# neuron.net
KiCad netlist of a schematic drawn in EAGLE
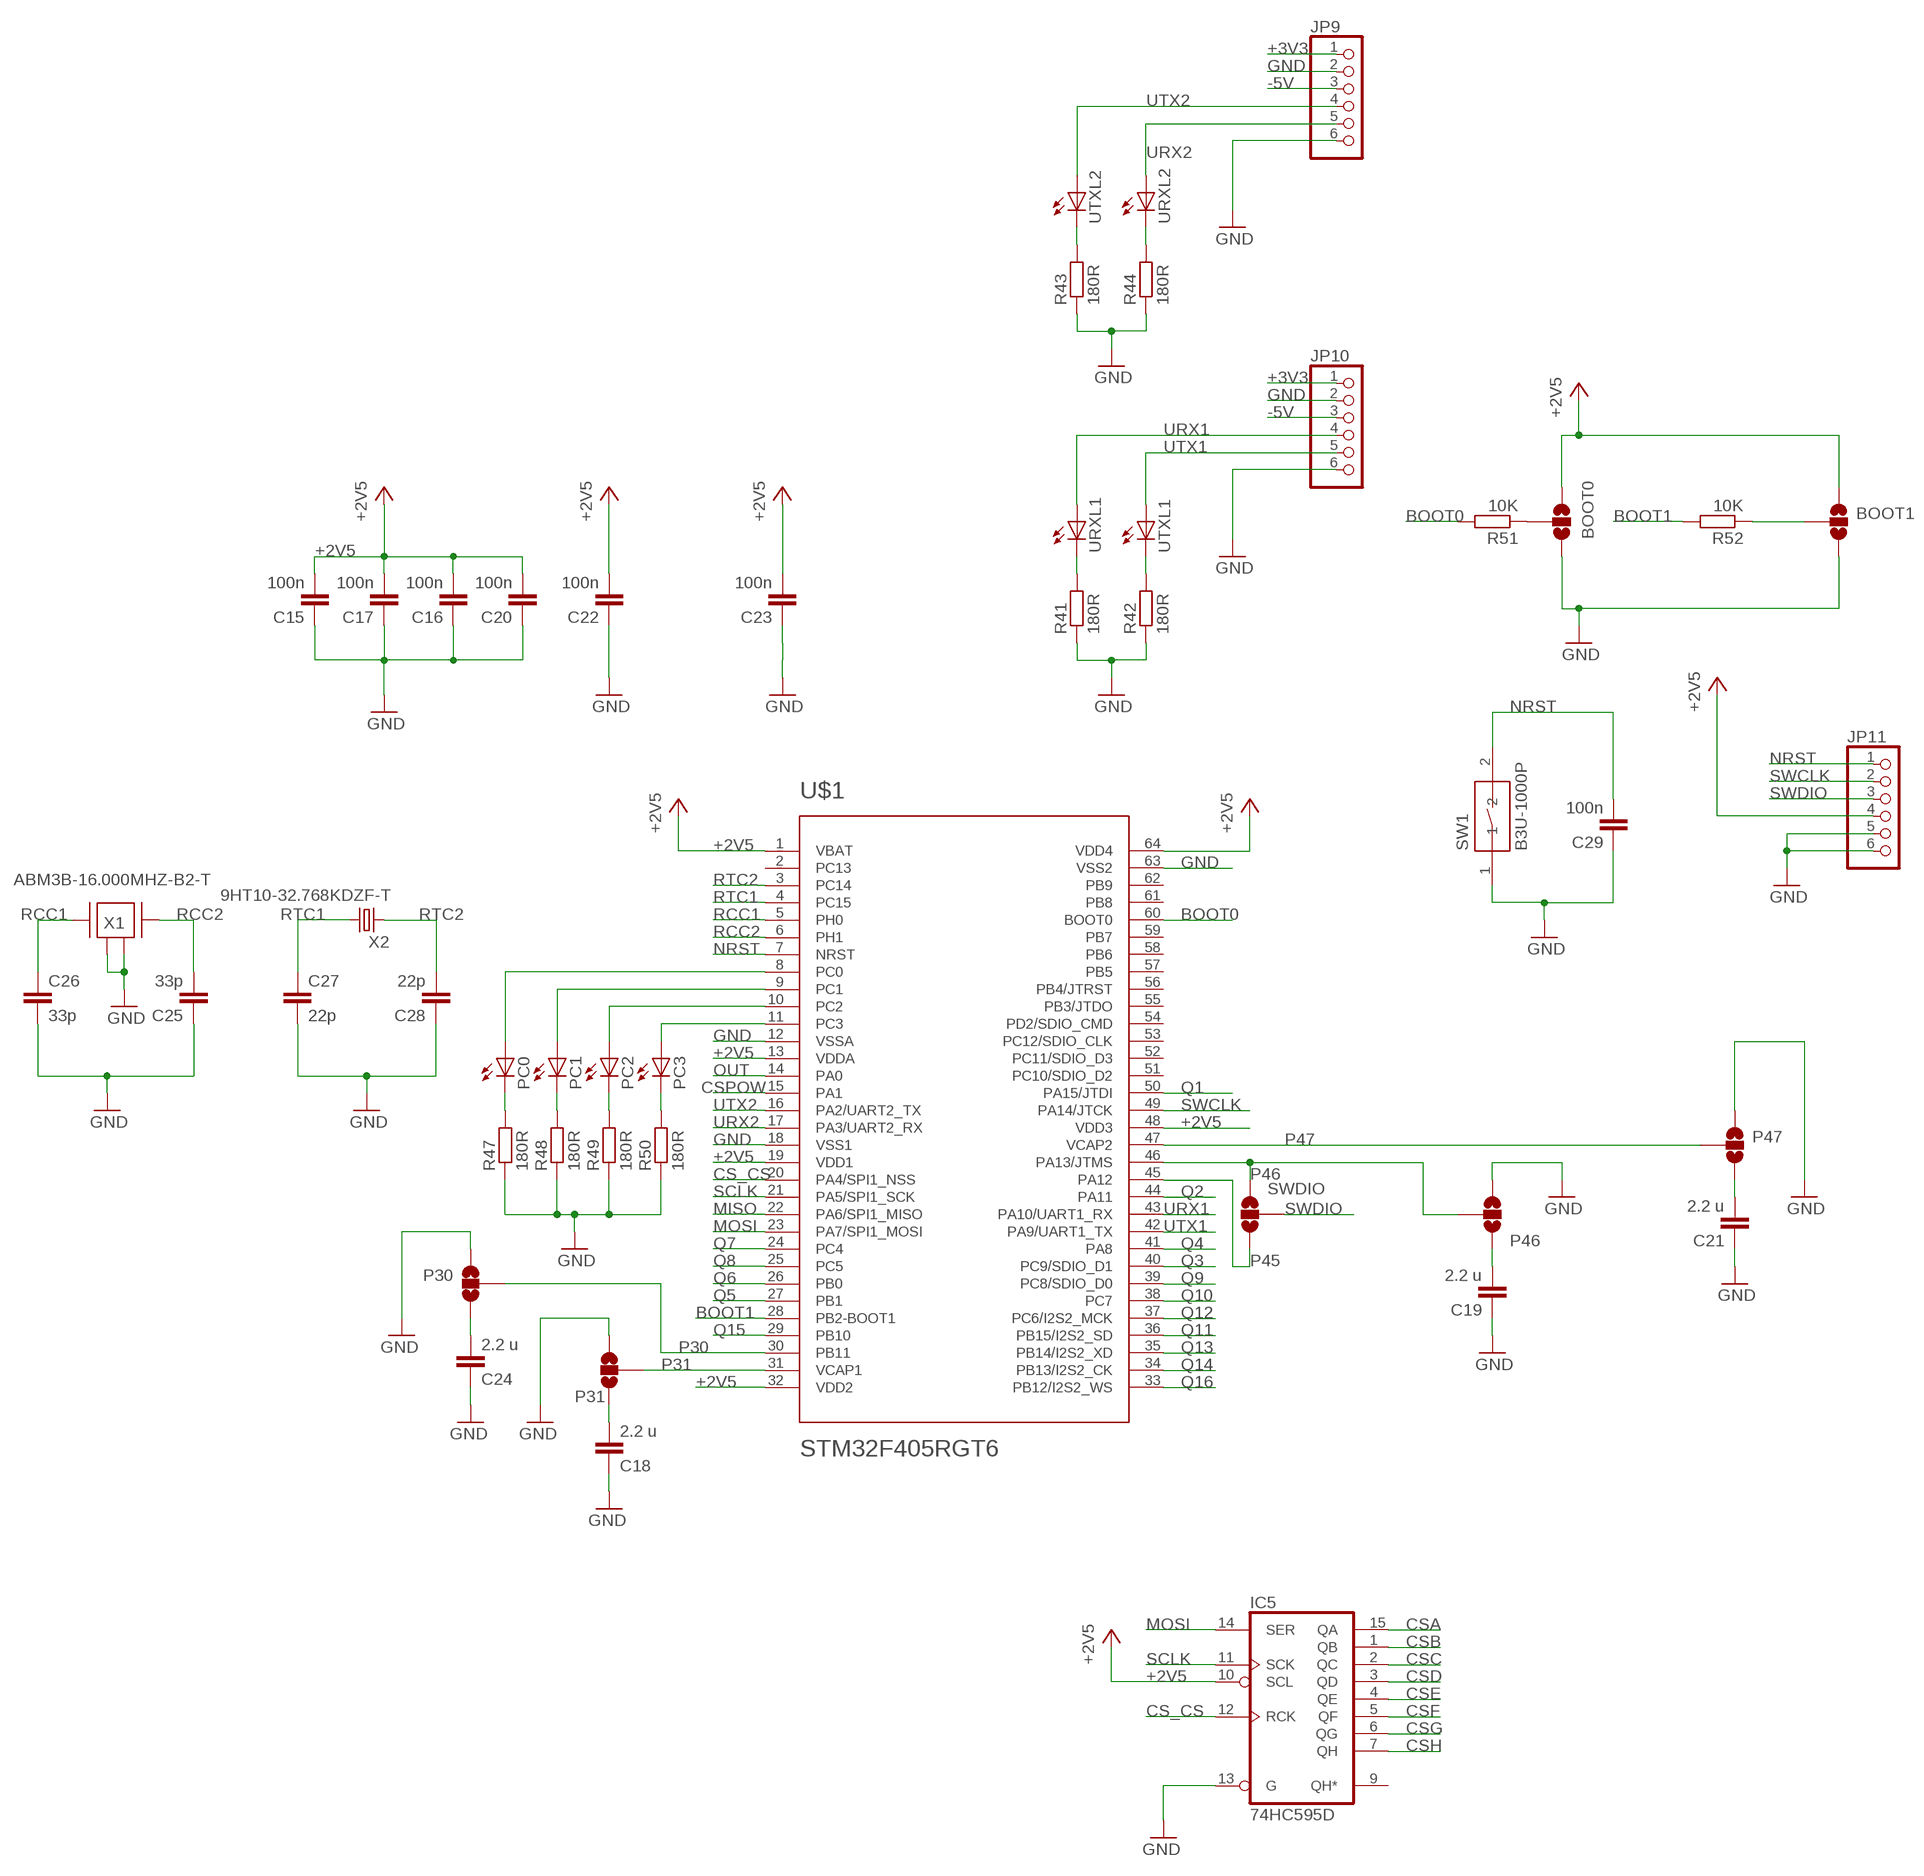
[diagram p0: schematic, sheet 1, part 1 of 2]
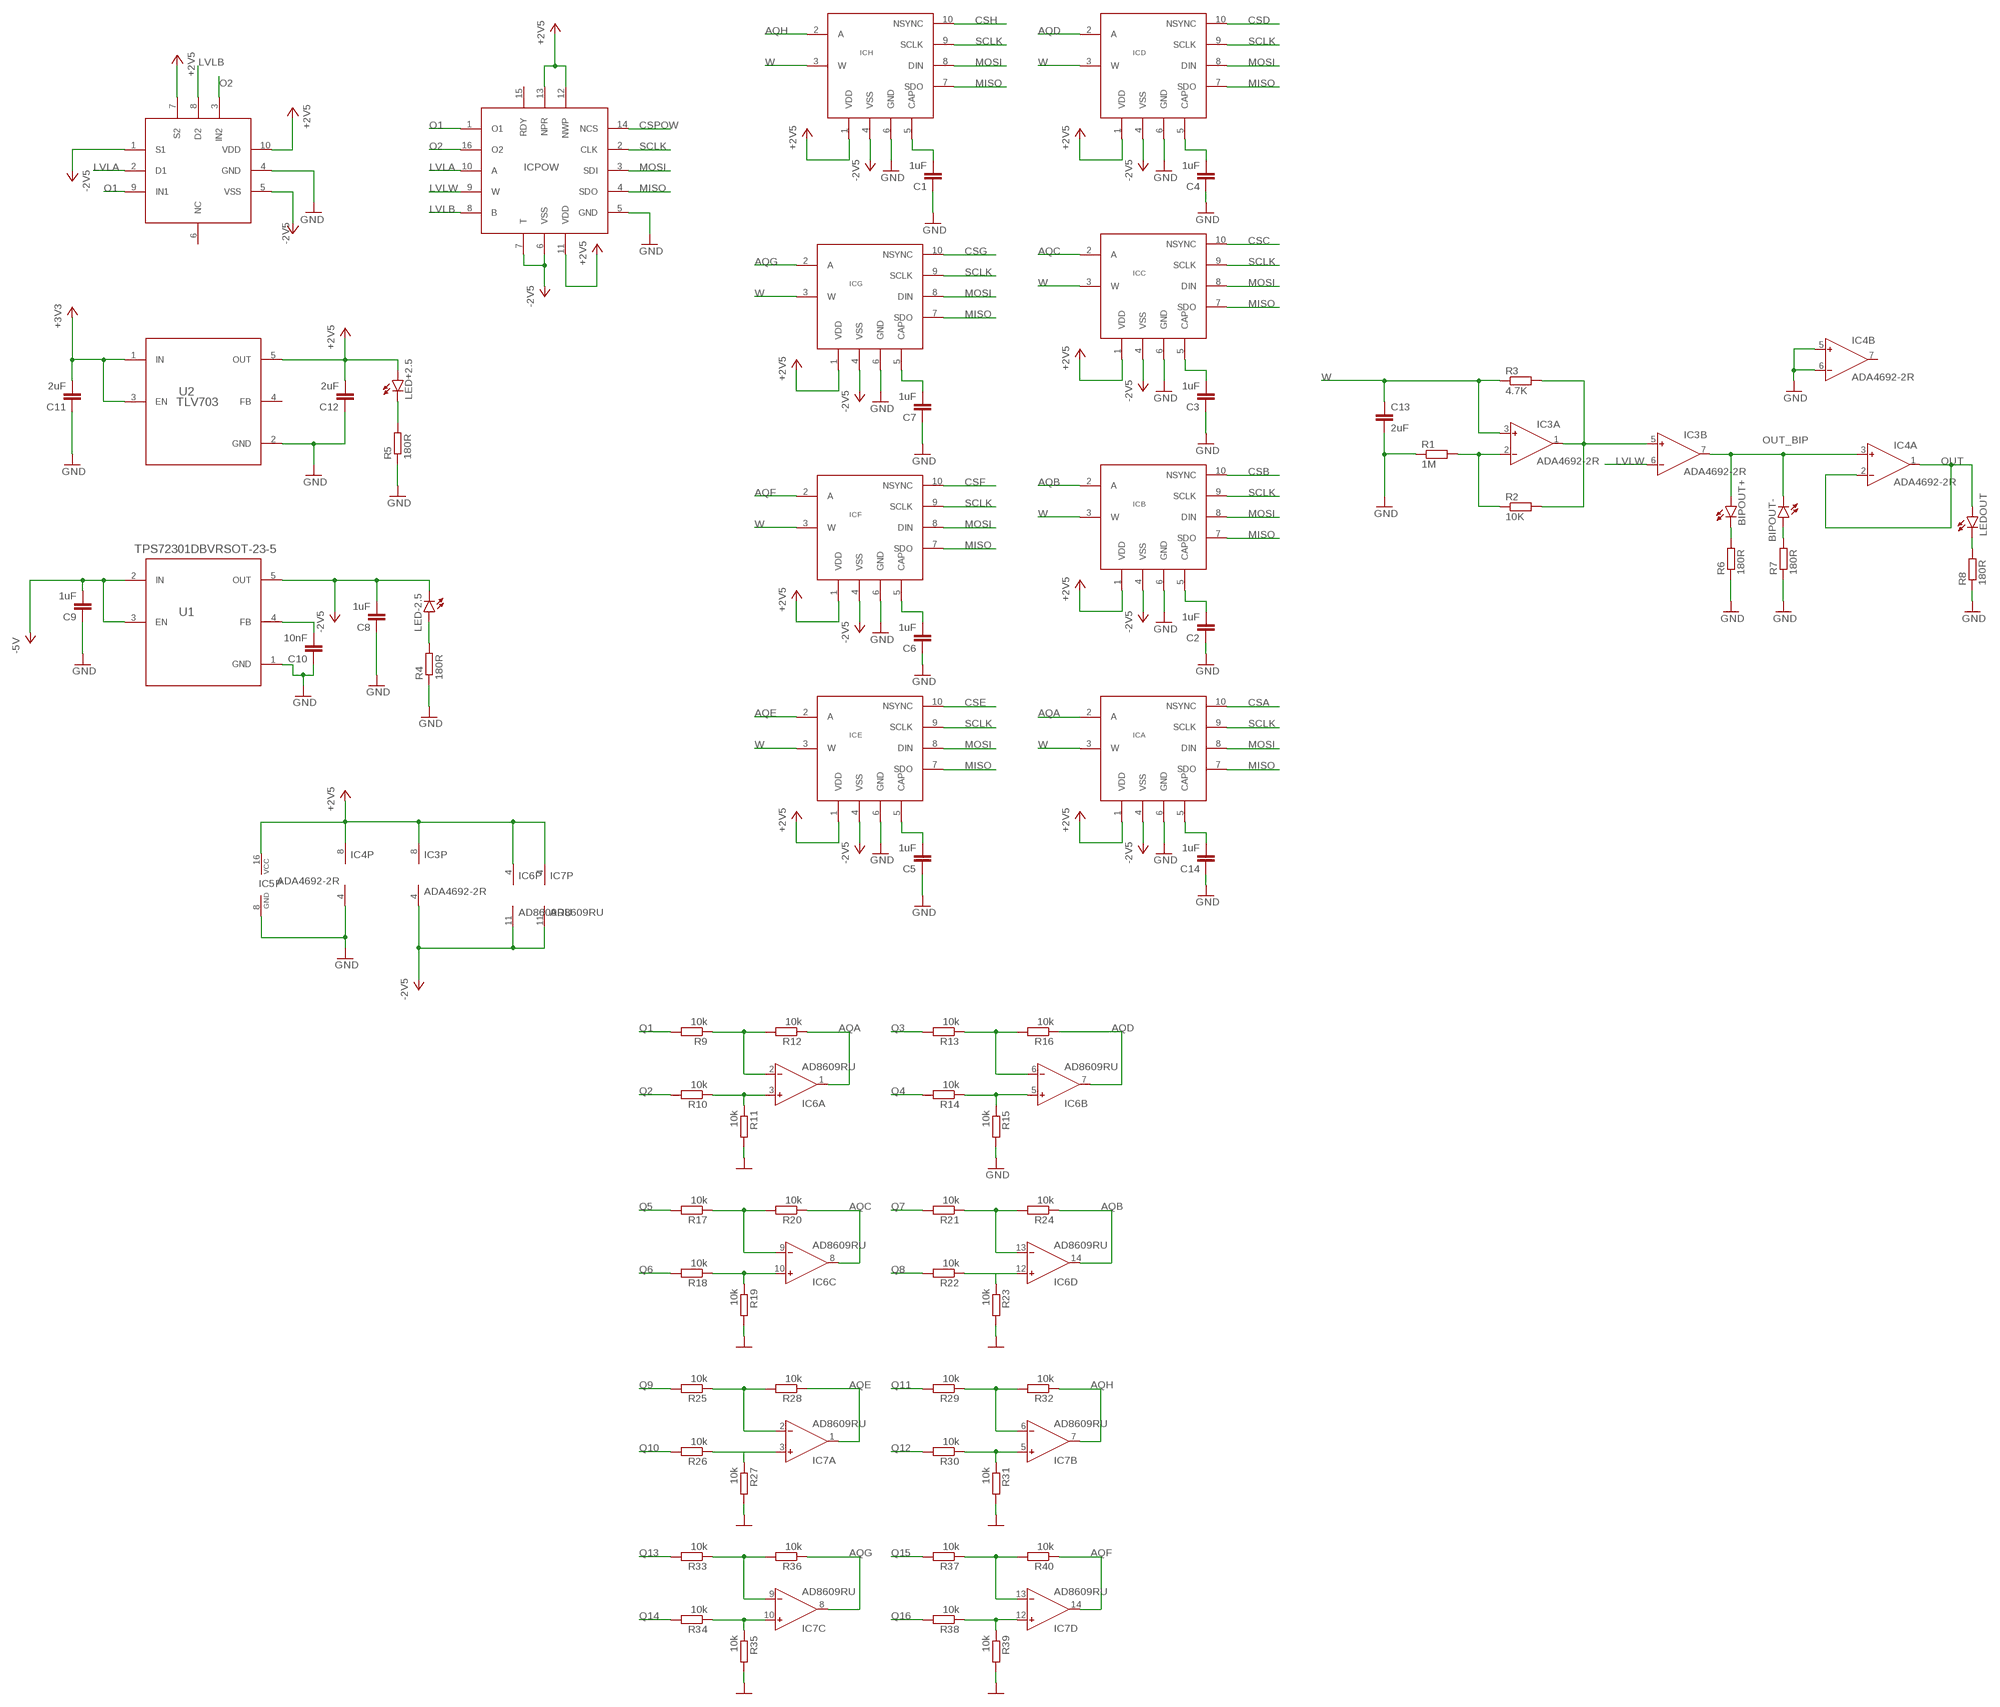
[diagram p1: schematic, sheet 1, part 2 of 2]

(export (version "E")
  (design (tool "Eeschema 10.0.6"))
  (components
    (comp (ref "BIPOUT+")
      (value "LEDCHIPLED_0805")
      (footprint "eagle-import:CHIPLED_0805")
      (libsource (lib "eagle-import") (part "led_259_LEDCHIPLED_0805"))
    )
    (comp (ref "BIPOUT-")
      (value "LEDCHIPLED_0805")
      (footprint "eagle-import:CHIPLED_0805")
      (libsource (lib "eagle-import") (part "led_259_LEDCHIPLED_0805"))
    )
    (comp (ref "BOOT0")
      (value "JUMPER-SMT_3_NO_NO-SILK")
      (footprint "eagle-import:SMT-JUMPER_3_NO_NO-SILK")
      (libsource (lib "eagle-import") (part "JUMPER-SMT_3_NO_NO-SILK"))
    )
    (comp (ref "BOOT1")
      (value "JUMPER-SMT_3_NO_NO-SILK")
      (footprint "eagle-import:SMT-JUMPER_3_NO_NO-SILK")
      (libsource (lib "eagle-import") (part "JUMPER-SMT_3_NO_NO-SILK"))
    )
    (comp (ref "C1")
      (value "1uF")
      (footprint "eagle-import:C0603")
      (libsource (lib "eagle-import") (part "C-EUC0603"))
    )
    (comp (ref "C2")
      (value "1uF")
      (footprint "eagle-import:C0603")
      (libsource (lib "eagle-import") (part "C-EUC0603"))
    )
    (comp (ref "C3")
      (value "1uF")
      (footprint "eagle-import:C0603")
      (libsource (lib "eagle-import") (part "C-EUC0603"))
    )
    (comp (ref "C4")
      (value "1uF")
      (footprint "eagle-import:C0603")
      (libsource (lib "eagle-import") (part "C-EUC0603"))
    )
    (comp (ref "C5")
      (value "1uF")
      (footprint "eagle-import:C0603")
      (libsource (lib "eagle-import") (part "C-EUC0603"))
    )
    (comp (ref "C6")
      (value "1uF")
      (footprint "eagle-import:C0603")
      (libsource (lib "eagle-import") (part "C-EUC0603"))
    )
    (comp (ref "C7")
      (value "1uF")
      (footprint "eagle-import:C0603")
      (libsource (lib "eagle-import") (part "C-EUC0603"))
    )
    (comp (ref "C8")
      (value "1uF")
      (footprint "eagle-import:C0603")
      (libsource (lib "eagle-import") (part "C-EUC0603"))
    )
    (comp (ref "C9")
      (value "1uF")
      (footprint "eagle-import:C0603")
      (libsource (lib "eagle-import") (part "C-EUC0603"))
    )
    (comp (ref "C10")
      (value "10nF")
      (footprint "eagle-import:C0603")
      (libsource (lib "eagle-import") (part "C-EUC0603"))
    )
    (comp (ref "C11")
      (value "2uF")
      (footprint "eagle-import:C0603")
      (libsource (lib "eagle-import") (part "C-EUC0603"))
    )
    (comp (ref "C12")
      (value "2uF")
      (footprint "eagle-import:C0603")
      (libsource (lib "eagle-import") (part "C-EUC0603"))
    )
    (comp (ref "C13")
      (value "2uF")
      (footprint "eagle-import:C0603K")
      (libsource (lib "eagle-import") (part "C-EUC0603K"))
    )
    (comp (ref "C14")
      (value "1uF")
      (footprint "eagle-import:C0603")
      (libsource (lib "eagle-import") (part "C-EUC0603"))
    )
    (comp (ref "C15")
      (value "100n")
      (footprint "eagle-import:C0603K")
      (libsource (lib "eagle-import") (part "C-EUC0603K"))
    )
    (comp (ref "C16")
      (value "100n")
      (footprint "eagle-import:C0603K")
      (libsource (lib "eagle-import") (part "C-EUC0603K"))
    )
    (comp (ref "C17")
      (value "100n")
      (footprint "eagle-import:C0603K")
      (libsource (lib "eagle-import") (part "C-EUC0603K"))
    )
    (comp (ref "C18")
      (value "2.2 u")
      (footprint "eagle-import:C0603K")
      (libsource (lib "eagle-import") (part "C-EUC0603K"))
    )
    (comp (ref "C19")
      (value "2.2 u")
      (footprint "eagle-import:C0603K")
      (libsource (lib "eagle-import") (part "C-EUC0603K"))
    )
    (comp (ref "C20")
      (value "100n")
      (footprint "eagle-import:C0603K")
      (libsource (lib "eagle-import") (part "C-EUC0603K"))
    )
    (comp (ref "C21")
      (value "2.2 u")
      (footprint "eagle-import:C0603K")
      (libsource (lib "eagle-import") (part "C-EUC0603K"))
    )
    (comp (ref "C22")
      (value "100n")
      (footprint "eagle-import:C0603K")
      (libsource (lib "eagle-import") (part "C-EUC0603K"))
    )
    (comp (ref "C23")
      (value "100n")
      (footprint "eagle-import:C0603K")
      (libsource (lib "eagle-import") (part "C-EUC0603K"))
    )
    (comp (ref "C24")
      (value "2.2 u")
      (footprint "eagle-import:C0603K")
      (libsource (lib "eagle-import") (part "C-EUC0603K"))
    )
    (comp (ref "C25")
      (value "33p")
      (footprint "eagle-import:C0603K")
      (libsource (lib "eagle-import") (part "C-EUC0603K"))
    )
    (comp (ref "C26")
      (value "33p")
      (footprint "eagle-import:C0603K")
      (libsource (lib "eagle-import") (part "C-EUC0603K"))
    )
    (comp (ref "C27")
      (value "22p")
      (footprint "eagle-import:C0603K")
      (libsource (lib "eagle-import") (part "C-EUC0603K"))
    )
    (comp (ref "C28")
      (value "22p")
      (footprint "eagle-import:C0603K")
      (libsource (lib "eagle-import") (part "C-EUC0603K"))
    )
    (comp (ref "C29")
      (value "100n")
      (footprint "eagle-import:C0603K")
      (libsource (lib "eagle-import") (part "C-EUC0603K"))
    )
    (comp (ref "IC3")
      (value "ADA4692-2R")
      (footprint "eagle-import:SO8")
      (fields (field (name "MPN") "ADA4692-2ARZ"))
      (libsource (lib "eagle-import") (part "ADA4692-2R"))
    )
    (comp (ref "IC4")
      (value "ADA4692-2R")
      (footprint "eagle-import:SO8")
      (fields (field (name "MPN") "ADA4692-2ARZ"))
      (libsource (lib "eagle-import") (part "ADA4692-2R"))
    )
    (comp (ref "IC5")
      (value "74HC595D")
      (footprint "eagle-import:SO16")
      (libsource (lib "eagle-import") (part "74595DHC"))
    )
    (comp (ref "IC6")
      (value "AD8609RU")
      (footprint "eagle-import:TSSOP14")
      (fields (field (name "MF") "ALTERA CORPORATION") (field (name "MPN") "AD8609ARUZ"))
      (libsource (lib "eagle-import") (part "AD8609RU"))
    )
    (comp (ref "IC7")
      (value "AD8609RU")
      (footprint "eagle-import:TSSOP14")
      (fields (field (name "MF") "ALTERA CORPORATION") (field (name "MPN") "AD8609ARUZ"))
      (libsource (lib "eagle-import") (part "AD8609RU"))
    )
    (comp (ref "ICA")
      (value "AD5270MSOP10")
      (footprint "eagle-import:MSOP10")
      (libsource (lib "eagle-import") (part "AD5270MSOP10"))
    )
    (comp (ref "ICB")
      (value "AD5270MSOP10")
      (footprint "eagle-import:MSOP10")
      (libsource (lib "eagle-import") (part "AD5270MSOP10"))
    )
    (comp (ref "ICC")
      (value "AD5270MSOP10")
      (footprint "eagle-import:MSOP10")
      (libsource (lib "eagle-import") (part "AD5270MSOP10"))
    )
    (comp (ref "ICD")
      (value "AD5270MSOP10")
      (footprint "eagle-import:MSOP10")
      (libsource (lib "eagle-import") (part "AD5270MSOP10"))
    )
    (comp (ref "ICE")
      (value "AD5270MSOP10")
      (footprint "eagle-import:MSOP10")
      (libsource (lib "eagle-import") (part "AD5270MSOP10"))
    )
    (comp (ref "ICF")
      (value "AD5270MSOP10")
      (footprint "eagle-import:MSOP10")
      (libsource (lib "eagle-import") (part "AD5270MSOP10"))
    )
    (comp (ref "ICG")
      (value "AD5270MSOP10")
      (footprint "eagle-import:MSOP10")
      (libsource (lib "eagle-import") (part "AD5270MSOP10"))
    )
    (comp (ref "ICH")
      (value "AD5270MSOP10")
      (footprint "eagle-import:MSOP10")
      (libsource (lib "eagle-import") (part "AD5270MSOP10"))
    )
    (comp (ref "ICPOW")
      (value "AD5231")
      (footprint "eagle-import:TSSOP16")
      (libsource (lib "eagle-import") (part "AD5231"))
    )
    (comp (ref "ICSW")
      (value "ADG621")
      (footprint "eagle-import:MSOP10")
      (libsource (lib "eagle-import") (part "ADG621"))
    )
    (comp (ref "JP9")
      (value "PINHD-1X6")
      (footprint "eagle-import:1X06")
      (libsource (lib "eagle-import") (part "PINHD-1X6"))
    )
    (comp (ref "JP10")
      (value "PINHD-1X6")
      (footprint "eagle-import:1X06")
      (libsource (lib "eagle-import") (part "PINHD-1X6"))
    )
    (comp (ref "JP11")
      (value "PINHD-1X6")
      (footprint "eagle-import:1X06")
      (libsource (lib "eagle-import") (part "PINHD-1X6"))
    )
    (comp (ref "LED+2.5")
      (value "LEDCHIPLED_0805")
      (footprint "eagle-import:CHIPLED_0805")
      (libsource (lib "eagle-import") (part "led_259_LEDCHIPLED_0805"))
    )
    (comp (ref "LED-2.5")
      (value "LEDCHIPLED_0805")
      (footprint "eagle-import:CHIPLED_0805")
      (libsource (lib "eagle-import") (part "led_259_LEDCHIPLED_0805"))
    )
    (comp (ref "LEDOUT")
      (value "LEDCHIPLED_0805")
      (footprint "eagle-import:CHIPLED_0805")
      (libsource (lib "eagle-import") (part "led_259_LEDCHIPLED_0805"))
    )
    (comp (ref "P30")
      (value "JUMPER-SMT_3_NO_NO-SILK")
      (footprint "eagle-import:SMT-JUMPER_3_NO_NO-SILK")
      (libsource (lib "eagle-import") (part "JUMPER-SMT_3_NO_NO-SILK"))
    )
    (comp (ref "P31")
      (value "JUMPER-SMT_3_NO_NO-SILK")
      (footprint "eagle-import:SMT-JUMPER_3_NO_NO-SILK")
      (libsource (lib "eagle-import") (part "JUMPER-SMT_3_NO_NO-SILK"))
    )
    (comp (ref "P46")
      (value "JUMPER-SMT_3_NO_NO-SILK")
      (footprint "eagle-import:SMT-JUMPER_3_NO_NO-SILK")
      (libsource (lib "eagle-import") (part "JUMPER-SMT_3_NO_NO-SILK"))
    )
    (comp (ref "P47")
      (value "JUMPER-SMT_3_NO_NO-SILK")
      (footprint "eagle-import:SMT-JUMPER_3_NO_NO-SILK")
      (libsource (lib "eagle-import") (part "JUMPER-SMT_3_NO_NO-SILK"))
    )
    (comp (ref "PC0")
      (value "LEDCHIPLED_0805")
      (footprint "eagle-import:CHIPLED_0805")
      (libsource (lib "eagle-import") (part "LEDCHIPLED_0805"))
    )
    (comp (ref "PC1")
      (value "LEDCHIPLED_0805")
      (footprint "eagle-import:CHIPLED_0805")
      (libsource (lib "eagle-import") (part "LEDCHIPLED_0805"))
    )
    (comp (ref "PC2")
      (value "LEDCHIPLED_0805")
      (footprint "eagle-import:CHIPLED_0805")
      (libsource (lib "eagle-import") (part "LEDCHIPLED_0805"))
    )
    (comp (ref "PC3")
      (value "LEDCHIPLED_0805")
      (footprint "eagle-import:CHIPLED_0805")
      (libsource (lib "eagle-import") (part "LEDCHIPLED_0805"))
    )
    (comp (ref "R1")
      (value "1M")
      (footprint "eagle-import:R0603")
      (libsource (lib "eagle-import") (part "R-EU_R0603"))
    )
    (comp (ref "R2")
      (value "10K")
      (footprint "eagle-import:R0603")
      (libsource (lib "eagle-import") (part "R-EU_R0603"))
    )
    (comp (ref "R3")
      (value "4.7K")
      (footprint "eagle-import:R0603")
      (libsource (lib "eagle-import") (part "R-EU_R0603"))
    )
    (comp (ref "R4")
      (value "180R")
      (footprint "eagle-import:R0603")
      (libsource (lib "eagle-import") (part "R-EU_R0603"))
    )
    (comp (ref "R5")
      (value "180R")
      (footprint "eagle-import:R0603")
      (libsource (lib "eagle-import") (part "R-EU_R0603"))
    )
    (comp (ref "R6")
      (value "180R")
      (footprint "eagle-import:R0603")
      (libsource (lib "eagle-import") (part "R-EU_R0603"))
    )
    (comp (ref "R7")
      (value "180R")
      (footprint "eagle-import:R0603")
      (libsource (lib "eagle-import") (part "R-EU_R0603"))
    )
    (comp (ref "R8")
      (value "180R")
      (footprint "eagle-import:R0603")
      (libsource (lib "eagle-import") (part "R-EU_R0603"))
    )
    (comp (ref "R9")
      (value "10k")
      (footprint "eagle-import:R0603")
      (libsource (lib "eagle-import") (part "R-EU_R0603"))
    )
    (comp (ref "R10")
      (value "10k")
      (footprint "eagle-import:R0603")
      (libsource (lib "eagle-import") (part "R-EU_R0603"))
    )
    (comp (ref "R11")
      (value "10k")
      (footprint "eagle-import:R0603")
      (libsource (lib "eagle-import") (part "R-EU_R0603"))
    )
    (comp (ref "R12")
      (value "10k")
      (footprint "eagle-import:R0603")
      (libsource (lib "eagle-import") (part "R-EU_R0603"))
    )
    (comp (ref "R13")
      (value "10k")
      (footprint "eagle-import:R0603")
      (libsource (lib "eagle-import") (part "R-EU_R0603"))
    )
    (comp (ref "R14")
      (value "10k")
      (footprint "eagle-import:R0603")
      (libsource (lib "eagle-import") (part "R-EU_R0603"))
    )
    (comp (ref "R15")
      (value "10k")
      (footprint "eagle-import:R0603")
      (libsource (lib "eagle-import") (part "R-EU_R0603"))
    )
    (comp (ref "R16")
      (value "10k")
      (footprint "eagle-import:R0603")
      (libsource (lib "eagle-import") (part "R-EU_R0603"))
    )
    (comp (ref "R17")
      (value "10k")
      (footprint "eagle-import:R0603")
      (libsource (lib "eagle-import") (part "R-EU_R0603"))
    )
    (comp (ref "R18")
      (value "10k")
      (footprint "eagle-import:R0603")
      (libsource (lib "eagle-import") (part "R-EU_R0603"))
    )
    (comp (ref "R19")
      (value "10k")
      (footprint "eagle-import:R0603")
      (libsource (lib "eagle-import") (part "R-EU_R0603"))
    )
    (comp (ref "R20")
      (value "10k")
      (footprint "eagle-import:R0603")
      (libsource (lib "eagle-import") (part "R-EU_R0603"))
    )
    (comp (ref "R21")
      (value "10k")
      (footprint "eagle-import:R0603")
      (libsource (lib "eagle-import") (part "R-EU_R0603"))
    )
    (comp (ref "R22")
      (value "10k")
      (footprint "eagle-import:R0603")
      (libsource (lib "eagle-import") (part "R-EU_R0603"))
    )
    (comp (ref "R23")
      (value "10k")
      (footprint "eagle-import:R0603")
      (libsource (lib "eagle-import") (part "R-EU_R0603"))
    )
    (comp (ref "R24")
      (value "10k")
      (footprint "eagle-import:R0603")
      (libsource (lib "eagle-import") (part "R-EU_R0603"))
    )
    (comp (ref "R25")
      (value "10k")
      (footprint "eagle-import:R0603")
      (libsource (lib "eagle-import") (part "R-EU_R0603"))
    )
    (comp (ref "R26")
      (value "10k")
      (footprint "eagle-import:R0603")
      (libsource (lib "eagle-import") (part "R-EU_R0603"))
    )
    (comp (ref "R27")
      (value "10k")
      (footprint "eagle-import:R0603")
      (libsource (lib "eagle-import") (part "R-EU_R0603"))
    )
    (comp (ref "R28")
      (value "10k")
      (footprint "eagle-import:R0603")
      (libsource (lib "eagle-import") (part "R-EU_R0603"))
    )
    (comp (ref "R29")
      (value "10k")
      (footprint "eagle-import:R0603")
      (libsource (lib "eagle-import") (part "R-EU_R0603"))
    )
    (comp (ref "R30")
      (value "10k")
      (footprint "eagle-import:R0603")
      (libsource (lib "eagle-import") (part "R-EU_R0603"))
    )
    (comp (ref "R31")
      (value "10k")
      (footprint "eagle-import:R0603")
      (libsource (lib "eagle-import") (part "R-EU_R0603"))
    )
    (comp (ref "R32")
      (value "10k")
      (footprint "eagle-import:R0603")
      (libsource (lib "eagle-import") (part "R-EU_R0603"))
    )
    (comp (ref "R33")
      (value "10k")
      (footprint "eagle-import:R0603")
      (libsource (lib "eagle-import") (part "R-EU_R0603"))
    )
    (comp (ref "R34")
      (value "10k")
      (footprint "eagle-import:R0603")
      (libsource (lib "eagle-import") (part "R-EU_R0603"))
    )
    (comp (ref "R35")
      (value "10k")
      (footprint "eagle-import:R0603")
      (libsource (lib "eagle-import") (part "R-EU_R0603"))
    )
    (comp (ref "R36")
      (value "10k")
      (footprint "eagle-import:R0603")
      (libsource (lib "eagle-import") (part "R-EU_R0603"))
    )
    (comp (ref "R37")
      (value "10k")
      (footprint "eagle-import:R0603")
      (libsource (lib "eagle-import") (part "R-EU_R0603"))
    )
    (comp (ref "R38")
      (value "10k")
      (footprint "eagle-import:R0603")
      (libsource (lib "eagle-import") (part "R-EU_R0603"))
    )
    (comp (ref "R39")
      (value "10k")
      (footprint "eagle-import:R0603")
      (libsource (lib "eagle-import") (part "R-EU_R0603"))
    )
    (comp (ref "R40")
      (value "10k")
      (footprint "eagle-import:R0603")
      (libsource (lib "eagle-import") (part "R-EU_R0603"))
    )
    (comp (ref "R41")
      (value "180R")
      (footprint "eagle-import:R0603")
      (libsource (lib "eagle-import") (part "R-EU_R0603"))
    )
    (comp (ref "R42")
      (value "180R")
      (footprint "eagle-import:R0603")
      (libsource (lib "eagle-import") (part "R-EU_R0603"))
    )
    (comp (ref "R43")
      (value "180R")
      (footprint "eagle-import:R0603")
      (libsource (lib "eagle-import") (part "R-EU_R0603"))
    )
    (comp (ref "R44")
      (value "180R")
      (footprint "eagle-import:R0603")
      (libsource (lib "eagle-import") (part "R-EU_R0603"))
    )
    (comp (ref "R47")
      (value "180R")
      (footprint "eagle-import:R0603")
      (libsource (lib "eagle-import") (part "R-EU_R0603"))
    )
    (comp (ref "R48")
      (value "180R")
      (footprint "eagle-import:R0603")
      (libsource (lib "eagle-import") (part "R-EU_R0603"))
    )
    (comp (ref "R49")
      (value "180R")
      (footprint "eagle-import:R0603")
      (libsource (lib "eagle-import") (part "R-EU_R0603"))
    )
    (comp (ref "R50")
      (value "180R")
      (footprint "eagle-import:R0603")
      (libsource (lib "eagle-import") (part "R-EU_R0603"))
    )
    (comp (ref "R51")
      (value "10K")
      (footprint "eagle-import:R0603")
      (libsource (lib "eagle-import") (part "R-EU_R0603"))
    )
    (comp (ref "R52")
      (value "10K")
      (footprint "eagle-import:R0603")
      (libsource (lib "eagle-import") (part "R-EU_R0603"))
    )
    (comp (ref "SW1")
      (value "B3U-1000P")
      (footprint "eagle-import:B3U-1000P")
      (fields
        (field (name "DIGI_KEY_PART_NUMBER") "SW1020CT-ND")
        (field (name "MANUFACTURER") "Omron Electronics Inc-EMC Div")
        (field (name "CREATED_BY") "PCBLayout.com")
      )
      (libsource (lib "eagle-import") (part "B3U-1000P"))
    )
    (comp (ref "SWDIO")
      (value "JUMPER-SMT_3_NO_NO-SILK")
      (footprint "eagle-import:SMT-JUMPER_3_NO_NO-SILK")
      (libsource (lib "eagle-import") (part "JUMPER-SMT_3_NO_NO-SILK"))
    )
    (comp (ref "U$1")
      (value "STM32F405RGT6")
      (footprint "eagle-import:TQFP64")
      (libsource (lib "eagle-import") (part "STM32F405RG"))
    )
    (comp (ref "U1")
      (value "TPS72301DBVRSOT-23-5")
      (footprint "eagle-import:SOT95P280X145-5N")
      (libsource (lib "eagle-import") (part "TPS72301DBVRSOT-23-5"))
    )
    (comp (ref "U2")
      (value "TLV703")
      (footprint "eagle-import:SOT95P280X145-5N")
      (libsource (lib "eagle-import") (part "TLV703"))
    )
    (comp (ref "URXL1")
      (value "LEDCHIPLED_0805")
      (footprint "eagle-import:CHIPLED_0805")
      (libsource (lib "eagle-import") (part "LEDCHIPLED_0805"))
    )
    (comp (ref "URXL2")
      (value "LEDCHIPLED_0805")
      (footprint "eagle-import:CHIPLED_0805")
      (libsource (lib "eagle-import") (part "LEDCHIPLED_0805"))
    )
    (comp (ref "UTXL1")
      (value "LEDCHIPLED_0805")
      (footprint "eagle-import:CHIPLED_0805")
      (libsource (lib "eagle-import") (part "LEDCHIPLED_0805"))
    )
    (comp (ref "UTXL2")
      (value "LEDCHIPLED_0805")
      (footprint "eagle-import:CHIPLED_0805")
      (libsource (lib "eagle-import") (part "LEDCHIPLED_0805"))
    )
    (comp (ref "X1")
      (value "ABM3B-16.000MHZ-B2-T")
      (footprint "eagle-import:ABM3B-16.000MHZ-B2-T")
      (fields
        (field (name "DIGIKEY_PART_NUMBER") "535-9122-2-ND")
        (field (name "MANUFACTURER") "Abracon LLC")
        (field (name "CREATED_BY") "PCBLayout.com")
      )
      (libsource (lib "eagle-import") (part "ABM3B-16.000MHZ-B2-T"))
    )
    (comp (ref "X2")
      (value "9HT10-32.768KDZF-T")
      (footprint "eagle-import:9HT10-32.768KDZF-T")
      (fields
        (field (name "DIGIKEY_PART_NUMBER") "887-1504-2-ND")
        (field (name "MANUFACTURER") "TXC CORPORATION")
        (field (name "CREATED_BY") "PCBLayout.com")
      )
      (libsource (lib "eagle-import") (part "9HT10-32.768KDZF-T"))
    )
  )
  (nets
    (net (code "1") (name "+2V5") (class "Default")
      (node (ref "BOOT0") (pin "1") (pinfunction "1_1") (pintype "passive"))
      (node (ref "BOOT1") (pin "1") (pinfunction "1_1") (pintype "passive"))
      (node (ref "C12") (pin "2") (pinfunction "2_2") (pintype "passive"))
      (node (ref "C15") (pin "2") (pinfunction "2_2") (pintype "passive"))
      (node (ref "C16") (pin "2") (pinfunction "2_2") (pintype "passive"))
      (node (ref "C17") (pin "2") (pinfunction "2_2") (pintype "passive"))
      (node (ref "C20") (pin "2") (pinfunction "2_2") (pintype "passive"))
      (node (ref "C22") (pin "2") (pinfunction "2_2") (pintype "passive"))
      (node (ref "C23") (pin "2") (pinfunction "2_2") (pintype "passive"))
      (node (ref "IC3") (pin "8") (pinfunction "V+_8") (pintype "power_in"))
      (node (ref "IC4") (pin "8") (pinfunction "V+_8") (pintype "power_in"))
      (node (ref "IC5") (pin "10") (pinfunction "SCL_10") (pintype "input"))
      (node (ref "IC5") (pin "16") (pinfunction "VCC_16") (pintype "power_in"))
      (node (ref "IC6") (pin "4") (pinfunction "V+_4") (pintype "power_in"))
      (node (ref "IC7") (pin "4") (pinfunction "V+_4") (pintype "power_in"))
      (node (ref "ICA") (pin "1") (pinfunction "VDD_1") (pintype "bidirectional"))
      (node (ref "ICB") (pin "1") (pinfunction "VDD_1") (pintype "bidirectional"))
      (node (ref "ICC") (pin "1") (pinfunction "VDD_1") (pintype "bidirectional"))
      (node (ref "ICD") (pin "1") (pinfunction "VDD_1") (pintype "bidirectional"))
      (node (ref "ICE") (pin "1") (pinfunction "VDD_1") (pintype "bidirectional"))
      (node (ref "ICF") (pin "1") (pinfunction "VDD_1") (pintype "bidirectional"))
      (node (ref "ICG") (pin "1") (pinfunction "VDD_1") (pintype "bidirectional"))
      (node (ref "ICH") (pin "1") (pinfunction "VDD_1") (pintype "bidirectional"))
      (node (ref "ICPOW") (pin "11") (pinfunction "VDD_11") (pintype "bidirectional"))
      (node (ref "ICPOW") (pin "12") (pinfunction "NWP_12") (pintype "bidirectional"))
      (node (ref "ICPOW") (pin "13") (pinfunction "NPR_13") (pintype "bidirectional"))
      (node (ref "ICSW") (pin "10") (pinfunction "VDD_10") (pintype "bidirectional"))
      (node (ref "ICSW") (pin "7") (pinfunction "S2_7") (pintype "bidirectional"))
      (node (ref "JP11") (pin "4") (pinfunction "4_4") (pintype "passive"))
      (node (ref "LED+2.5") (pin "A") (pinfunction "A_A") (pintype "passive"))
      (node (ref "U$1") (pin "1") (pinfunction "VBAT_1") (pintype "bidirectional"))
      (node (ref "U$1") (pin "13") (pinfunction "VDDA_13") (pintype "bidirectional"))
      (node (ref "U$1") (pin "19") (pinfunction "VDD1_19") (pintype "bidirectional"))
      (node (ref "U$1") (pin "32") (pinfunction "VDD2_32") (pintype "bidirectional"))
      (node (ref "U$1") (pin "48") (pinfunction "VDD3_48") (pintype "bidirectional"))
      (node (ref "U$1") (pin "64") (pinfunction "VDD4_64") (pintype "bidirectional"))
      (node (ref "U2") (pin "5") (pinfunction "OUT_5") (pintype "power_in"))
    )
    (net (code "2") (name "+3V3") (class "Default")
      (node (ref "C11") (pin "2") (pinfunction "2_2") (pintype "passive"))
      (node (ref "JP10") (pin "1") (pinfunction "1_1") (pintype "passive"))
      (node (ref "JP9") (pin "1") (pinfunction "1_1") (pintype "passive"))
      (node (ref "U2") (pin "1") (pinfunction "IN_1") (pintype "power_in"))
      (node (ref "U2") (pin "3") (pinfunction "EN_3") (pintype "input"))
    )
    (net (code "3") (name "-2V5") (class "Default")
      (node (ref "C8") (pin "2") (pinfunction "2_2") (pintype "passive"))
      (node (ref "IC3") (pin "4") (pinfunction "V-_4") (pintype "power_in"))
      (node (ref "IC6") (pin "11") (pinfunction "V-_11") (pintype "power_in"))
      (node (ref "IC7") (pin "11") (pinfunction "V-_11") (pintype "power_in"))
      (node (ref "ICA") (pin "4") (pinfunction "VSS_4") (pintype "bidirectional"))
      (node (ref "ICB") (pin "4") (pinfunction "VSS_4") (pintype "bidirectional"))
      (node (ref "ICC") (pin "4") (pinfunction "VSS_4") (pintype "bidirectional"))
      (node (ref "ICD") (pin "4") (pinfunction "VSS_4") (pintype "bidirectional"))
      (node (ref "ICE") (pin "4") (pinfunction "VSS_4") (pintype "bidirectional"))
      (node (ref "ICF") (pin "4") (pinfunction "VSS_4") (pintype "bidirectional"))
      (node (ref "ICG") (pin "4") (pinfunction "VSS_4") (pintype "bidirectional"))
      (node (ref "ICH") (pin "4") (pinfunction "VSS_4") (pintype "bidirectional"))
      (node (ref "ICPOW") (pin "6") (pinfunction "VSS_6") (pintype "bidirectional"))
      (node (ref "ICPOW") (pin "7") (pinfunction "T_7") (pintype "bidirectional"))
      (node (ref "ICSW") (pin "1") (pinfunction "S1_1") (pintype "bidirectional"))
      (node (ref "ICSW") (pin "5") (pinfunction "VSS_5") (pintype "bidirectional"))
      (node (ref "LED-2.5") (pin "C") (pinfunction "C_C") (pintype "passive"))
      (node (ref "U1") (pin "5") (pinfunction "OUT_5") (pintype "power_in"))
    )
    (net (code "4") (name "-5V") (class "Default")
      (node (ref "C9") (pin "2") (pinfunction "2_2") (pintype "passive"))
      (node (ref "JP10") (pin "3") (pinfunction "3_3") (pintype "passive"))
      (node (ref "JP9") (pin "3") (pinfunction "3_3") (pintype "passive"))
      (node (ref "U1") (pin "2") (pinfunction "IN_2") (pintype "power_in"))
      (node (ref "U1") (pin "3") (pinfunction "EN_3") (pintype "input"))
    )
    (net (code "5") (name "/AQA") (class "Default")
      (node (ref "IC6") (pin "1") (pinfunction "OUT_1") (pintype "output"))
      (node (ref "ICA") (pin "2") (pinfunction "A_2") (pintype "bidirectional"))
      (node (ref "R12") (pin "1") (pinfunction "1_1") (pintype "passive"))
    )
    (net (code "6") (name "/AQB") (class "Default")
      (node (ref "IC6") (pin "14") (pinfunction "OUT_14") (pintype "output"))
      (node (ref "ICB") (pin "2") (pinfunction "A_2") (pintype "bidirectional"))
      (node (ref "R24") (pin "1") (pinfunction "1_1") (pintype "passive"))
    )
    (net (code "7") (name "/AQC") (class "Default")
      (node (ref "IC6") (pin "8") (pinfunction "OUT_8") (pintype "output"))
      (node (ref "ICC") (pin "2") (pinfunction "A_2") (pintype "bidirectional"))
      (node (ref "R20") (pin "1") (pinfunction "1_1") (pintype "passive"))
    )
    (net (code "8") (name "/AQD") (class "Default")
      (node (ref "IC6") (pin "7") (pinfunction "OUT_7") (pintype "output"))
      (node (ref "ICD") (pin "2") (pinfunction "A_2") (pintype "bidirectional"))
      (node (ref "R16") (pin "1") (pinfunction "1_1") (pintype "passive"))
    )
    (net (code "9") (name "/AQE") (class "Default")
      (node (ref "IC7") (pin "1") (pinfunction "OUT_1") (pintype "output"))
      (node (ref "ICE") (pin "2") (pinfunction "A_2") (pintype "bidirectional"))
      (node (ref "R28") (pin "1") (pinfunction "1_1") (pintype "passive"))
    )
    (net (code "10") (name "/AQF") (class "Default")
      (node (ref "IC7") (pin "14") (pinfunction "OUT_14") (pintype "output"))
      (node (ref "ICF") (pin "2") (pinfunction "A_2") (pintype "bidirectional"))
      (node (ref "R40") (pin "1") (pinfunction "1_1") (pintype "passive"))
    )
    (net (code "11") (name "/AQG") (class "Default")
      (node (ref "IC7") (pin "8") (pinfunction "OUT_8") (pintype "output"))
      (node (ref "ICG") (pin "2") (pinfunction "A_2") (pintype "bidirectional"))
      (node (ref "R36") (pin "1") (pinfunction "1_1") (pintype "passive"))
    )
    (net (code "12") (name "/AQH") (class "Default")
      (node (ref "IC7") (pin "7") (pinfunction "OUT_7") (pintype "output"))
      (node (ref "ICH") (pin "2") (pinfunction "A_2") (pintype "bidirectional"))
      (node (ref "R32") (pin "1") (pinfunction "1_1") (pintype "passive"))
    )
    (net (code "13") (name "/BOOT0") (class "Default")
      (node (ref "R51") (pin "2") (pinfunction "2_2") (pintype "passive"))
      (node (ref "U$1") (pin "60") (pinfunction "BOOT0_60") (pintype "bidirectional"))
    )
    (net (code "14") (name "/BOOT1") (class "Default")
      (node (ref "R52") (pin "2") (pinfunction "2_2") (pintype "passive"))
      (node (ref "U$1") (pin "28") (pinfunction "PB2-BOOT1_28") (pintype "bidirectional"))
    )
    (net (code "15") (name "/CSA") (class "Default")
      (node (ref "IC5") (pin "15") (pinfunction "QA_15") (pintype "tri_state"))
      (node (ref "ICA") (pin "10") (pinfunction "NSYNC_10") (pintype "bidirectional"))
    )
    (net (code "16") (name "/CSB") (class "Default")
      (node (ref "IC5") (pin "1") (pinfunction "QB_1") (pintype "tri_state"))
      (node (ref "ICB") (pin "10") (pinfunction "NSYNC_10") (pintype "bidirectional"))
    )
    (net (code "17") (name "/CSC") (class "Default")
      (node (ref "IC5") (pin "2") (pinfunction "QC_2") (pintype "tri_state"))
      (node (ref "ICC") (pin "10") (pinfunction "NSYNC_10") (pintype "bidirectional"))
    )
    (net (code "18") (name "/CSD") (class "Default")
      (node (ref "IC5") (pin "3") (pinfunction "QD_3") (pintype "tri_state"))
      (node (ref "ICD") (pin "10") (pinfunction "NSYNC_10") (pintype "bidirectional"))
    )
    (net (code "19") (name "/CSE") (class "Default")
      (node (ref "IC5") (pin "4") (pinfunction "QE_4") (pintype "tri_state"))
      (node (ref "ICE") (pin "10") (pinfunction "NSYNC_10") (pintype "bidirectional"))
    )
    (net (code "20") (name "/CSF") (class "Default")
      (node (ref "IC5") (pin "5") (pinfunction "QF_5") (pintype "tri_state"))
      (node (ref "ICF") (pin "10") (pinfunction "NSYNC_10") (pintype "bidirectional"))
    )
    (net (code "21") (name "/CSG") (class "Default")
      (node (ref "IC5") (pin "6") (pinfunction "QG_6") (pintype "tri_state"))
      (node (ref "ICG") (pin "10") (pinfunction "NSYNC_10") (pintype "bidirectional"))
    )
    (net (code "22") (name "/CSH") (class "Default")
      (node (ref "IC5") (pin "7") (pinfunction "QH_7") (pintype "tri_state"))
      (node (ref "ICH") (pin "10") (pinfunction "NSYNC_10") (pintype "bidirectional"))
    )
    (net (code "23") (name "/CSPOW") (class "Default")
      (node (ref "ICPOW") (pin "14") (pinfunction "NCS_14") (pintype "bidirectional"))
      (node (ref "U$1") (pin "15") (pinfunction "PA1_15") (pintype "bidirectional"))
    )
    (net (code "24") (name "/CS_CS") (class "Default")
      (node (ref "IC5") (pin "12") (pinfunction "RCK_12") (pintype "input"))
      (node (ref "U$1") (pin "20") (pinfunction "PA4/SPI1_NSS_20") (pintype "bidirectional"))
    )
    (net (code "25") (name "/LVLA") (class "Default")
      (node (ref "ICPOW") (pin "10") (pinfunction "A_10") (pintype "bidirectional"))
      (node (ref "ICSW") (pin "2") (pinfunction "D1_2") (pintype "bidirectional"))
    )
    (net (code "26") (name "/LVLB") (class "Default")
      (node (ref "ICPOW") (pin "8") (pinfunction "B_8") (pintype "bidirectional"))
      (node (ref "ICSW") (pin "8") (pinfunction "D2_8") (pintype "bidirectional"))
    )
    (net (code "27") (name "/LVLW") (class "Default")
      (node (ref "IC3") (pin "6") (pinfunction "IN-_6") (pintype "input"))
      (node (ref "ICPOW") (pin "9") (pinfunction "W_9") (pintype "bidirectional"))
    )
    (net (code "28") (name "/MISO") (class "Default")
      (node (ref "ICA") (pin "7") (pinfunction "SDO_7") (pintype "bidirectional"))
      (node (ref "ICB") (pin "7") (pinfunction "SDO_7") (pintype "bidirectional"))
      (node (ref "ICC") (pin "7") (pinfunction "SDO_7") (pintype "bidirectional"))
      (node (ref "ICD") (pin "7") (pinfunction "SDO_7") (pintype "bidirectional"))
      (node (ref "ICE") (pin "7") (pinfunction "SDO_7") (pintype "bidirectional"))
      (node (ref "ICF") (pin "7") (pinfunction "SDO_7") (pintype "bidirectional"))
      (node (ref "ICG") (pin "7") (pinfunction "SDO_7") (pintype "bidirectional"))
      (node (ref "ICH") (pin "7") (pinfunction "SDO_7") (pintype "bidirectional"))
      (node (ref "ICPOW") (pin "4") (pinfunction "SDO_4") (pintype "bidirectional"))
      (node (ref "U$1") (pin "22") (pinfunction "PA6/SPI1_MISO_22") (pintype "bidirectional"))
    )
    (net (code "29") (name "/MOSI") (class "Default")
      (node (ref "IC5") (pin "14") (pinfunction "SER_14") (pintype "input"))
      (node (ref "ICA") (pin "8") (pinfunction "DIN_8") (pintype "bidirectional"))
      (node (ref "ICB") (pin "8") (pinfunction "DIN_8") (pintype "bidirectional"))
      (node (ref "ICC") (pin "8") (pinfunction "DIN_8") (pintype "bidirectional"))
      (node (ref "ICD") (pin "8") (pinfunction "DIN_8") (pintype "bidirectional"))
      (node (ref "ICE") (pin "8") (pinfunction "DIN_8") (pintype "bidirectional"))
      (node (ref "ICF") (pin "8") (pinfunction "DIN_8") (pintype "bidirectional"))
      (node (ref "ICG") (pin "8") (pinfunction "DIN_8") (pintype "bidirectional"))
      (node (ref "ICH") (pin "8") (pinfunction "DIN_8") (pintype "bidirectional"))
      (node (ref "ICPOW") (pin "3") (pinfunction "SDI_3") (pintype "bidirectional"))
      (node (ref "U$1") (pin "23") (pinfunction "PA7/SPI1_MOSI_23") (pintype "bidirectional"))
    )
    (net (code "30") (name "/NRST") (class "Default")
      (node (ref "C29") (pin "2") (pinfunction "2_2") (pintype "passive"))
      (node (ref "JP11") (pin "1") (pinfunction "1_1") (pintype "passive"))
      (node (ref "SW1") (pin "2") (pinfunction "2_2") (pintype "passive"))
      (node (ref "U$1") (pin "7") (pinfunction "NRST_7") (pintype "bidirectional"))
    )
    (net (code "31") (name "/O1") (class "Default")
      (node (ref "ICPOW") (pin "1") (pinfunction "O1_1") (pintype "bidirectional"))
      (node (ref "ICSW") (pin "9") (pinfunction "IN1_9") (pintype "bidirectional"))
    )
    (net (code "32") (name "/O2") (class "Default")
      (node (ref "ICPOW") (pin "16") (pinfunction "O2_16") (pintype "bidirectional"))
      (node (ref "ICSW") (pin "3") (pinfunction "IN2_3") (pintype "bidirectional"))
    )
    (net (code "33") (name "/OUT") (class "Default")
      (node (ref "IC4") (pin "1") (pinfunction "OUT_1") (pintype "output"))
      (node (ref "IC4") (pin "2") (pinfunction "IN-_2") (pintype "input"))
      (node (ref "LEDOUT") (pin "A") (pinfunction "A_A") (pintype "passive"))
      (node (ref "U$1") (pin "14") (pinfunction "PA0_14") (pintype "bidirectional"))
    )
    (net (code "34") (name "/OUT_BIP") (class "Default")
      (node (ref "BIPOUT+") (pin "A") (pinfunction "A_A") (pintype "passive"))
      (node (ref "BIPOUT-") (pin "C") (pinfunction "C_C") (pintype "passive"))
      (node (ref "IC3") (pin "7") (pinfunction "OUT_7") (pintype "output"))
      (node (ref "IC4") (pin "3") (pinfunction "IN+_3") (pintype "input"))
    )
    (net (code "35") (name "/P30") (class "Default")
      (node (ref "P30") (pin "2") (pinfunction "2_2") (pintype "passive"))
      (node (ref "U$1") (pin "30") (pinfunction "PB11_30") (pintype "bidirectional"))
    )
    (net (code "36") (name "/P31") (class "Default")
      (node (ref "P31") (pin "2") (pinfunction "2_2") (pintype "passive"))
      (node (ref "U$1") (pin "31") (pinfunction "VCAP1_31") (pintype "bidirectional"))
    )
    (net (code "37") (name "/P45") (class "Default")
      (node (ref "SWDIO") (pin "1") (pinfunction "1_1") (pintype "passive"))
      (node (ref "U$1") (pin "45") (pinfunction "PA12_45") (pintype "bidirectional"))
    )
    (net (code "38") (name "/P46") (class "Default")
      (node (ref "P46") (pin "2") (pinfunction "2_2") (pintype "passive"))
      (node (ref "SWDIO") (pin "3") (pinfunction "3_3") (pintype "passive"))
      (node (ref "U$1") (pin "46") (pinfunction "PA13/JTMS_46") (pintype "bidirectional"))
    )
    (net (code "39") (name "/P47") (class "Default")
      (node (ref "P47") (pin "2") (pinfunction "2_2") (pintype "passive"))
      (node (ref "U$1") (pin "47") (pinfunction "VCAP2_47") (pintype "bidirectional"))
    )
    (net (code "40") (name "/Q1") (class "Default")
      (node (ref "R9") (pin "2") (pinfunction "2_2") (pintype "passive"))
      (node (ref "U$1") (pin "50") (pinfunction "PA15/JTDI_50") (pintype "bidirectional"))
    )
    (net (code "41") (name "/Q2") (class "Default")
      (node (ref "R10") (pin "2") (pinfunction "2_2") (pintype "passive"))
      (node (ref "U$1") (pin "44") (pinfunction "PA11_44") (pintype "bidirectional"))
    )
    (net (code "42") (name "/Q3") (class "Default")
      (node (ref "R13") (pin "2") (pinfunction "2_2") (pintype "passive"))
      (node (ref "U$1") (pin "40") (pinfunction "PC9/SDIO_D1_40") (pintype "bidirectional"))
    )
    (net (code "43") (name "/Q4") (class "Default")
      (node (ref "R14") (pin "2") (pinfunction "2_2") (pintype "passive"))
      (node (ref "U$1") (pin "41") (pinfunction "PA8_41") (pintype "bidirectional"))
    )
    (net (code "44") (name "/Q5") (class "Default")
      (node (ref "R17") (pin "2") (pinfunction "2_2") (pintype "passive"))
      (node (ref "U$1") (pin "27") (pinfunction "PB1_27") (pintype "bidirectional"))
    )
    (net (code "45") (name "/Q6") (class "Default")
      (node (ref "R18") (pin "2") (pinfunction "2_2") (pintype "passive"))
      (node (ref "U$1") (pin "26") (pinfunction "PB0_26") (pintype "bidirectional"))
    )
    (net (code "46") (name "/Q7") (class "Default")
      (node (ref "R21") (pin "2") (pinfunction "2_2") (pintype "passive"))
      (node (ref "U$1") (pin "24") (pinfunction "PC4_24") (pintype "bidirectional"))
    )
    (net (code "47") (name "/Q8") (class "Default")
      (node (ref "R22") (pin "2") (pinfunction "2_2") (pintype "passive"))
      (node (ref "U$1") (pin "25") (pinfunction "PC5_25") (pintype "bidirectional"))
    )
    (net (code "48") (name "/Q9") (class "Default")
      (node (ref "R25") (pin "2") (pinfunction "2_2") (pintype "passive"))
      (node (ref "U$1") (pin "39") (pinfunction "PC8/SDIO_D0_39") (pintype "bidirectional"))
    )
    (net (code "49") (name "/Q10") (class "Default")
      (node (ref "R26") (pin "2") (pinfunction "2_2") (pintype "passive"))
      (node (ref "U$1") (pin "38") (pinfunction "PC7_38") (pintype "bidirectional"))
    )
    (net (code "50") (name "/Q11") (class "Default")
      (node (ref "R29") (pin "2") (pinfunction "2_2") (pintype "passive"))
      (node (ref "U$1") (pin "36") (pinfunction "PB15/I2S2_SD_36") (pintype "bidirectional"))
    )
    (net (code "51") (name "/Q12") (class "Default")
      (node (ref "R30") (pin "2") (pinfunction "2_2") (pintype "passive"))
      (node (ref "U$1") (pin "37") (pinfunction "PC6/I2S2_MCK_37") (pintype "bidirectional"))
    )
    (net (code "52") (name "/Q13") (class "Default")
      (node (ref "R33") (pin "2") (pinfunction "2_2") (pintype "passive"))
      (node (ref "U$1") (pin "35") (pinfunction "PB14/I2S2_XD_35") (pintype "bidirectional"))
    )
    (net (code "53") (name "/Q14") (class "Default")
      (node (ref "R34") (pin "2") (pinfunction "2_2") (pintype "passive"))
      (node (ref "U$1") (pin "34") (pinfunction "PB13/I2S2_CK_34") (pintype "bidirectional"))
    )
    (net (code "54") (name "/Q15") (class "Default")
      (node (ref "R37") (pin "2") (pinfunction "2_2") (pintype "passive"))
      (node (ref "U$1") (pin "29") (pinfunction "PB10_29") (pintype "bidirectional"))
    )
    (net (code "55") (name "/Q16") (class "Default")
      (node (ref "R38") (pin "2") (pinfunction "2_2") (pintype "passive"))
      (node (ref "U$1") (pin "33") (pinfunction "PB12/I2S2_WS_33") (pintype "bidirectional"))
    )
    (net (code "56") (name "/RCC1") (class "Default")
      (node (ref "C26") (pin "1") (pinfunction "1_1") (pintype "passive"))
      (node (ref "U$1") (pin "5") (pinfunction "PH0_5") (pintype "bidirectional"))
      (node (ref "X1") (pin "1") (pinfunction "1_1") (pintype "passive"))
    )
    (net (code "57") (name "/RCC2") (class "Default")
      (node (ref "C25") (pin "2") (pinfunction "2_2") (pintype "passive"))
      (node (ref "U$1") (pin "6") (pinfunction "PH1_6") (pintype "bidirectional"))
      (node (ref "X1") (pin "3") (pinfunction "3_3") (pintype "passive"))
    )
    (net (code "58") (name "/RTC1") (class "Default")
      (node (ref "C27") (pin "1") (pinfunction "1_1") (pintype "passive"))
      (node (ref "U$1") (pin "4") (pinfunction "PC15_4") (pintype "bidirectional"))
      (node (ref "X2") (pin "2") (pinfunction "2_2") (pintype "passive"))
    )
    (net (code "59") (name "/RTC2") (class "Default")
      (node (ref "C28") (pin "2") (pinfunction "2_2") (pintype "passive"))
      (node (ref "U$1") (pin "3") (pinfunction "PC14_3") (pintype "bidirectional"))
      (node (ref "X2") (pin "1") (pinfunction "1_1") (pintype "passive"))
    )
    (net (code "60") (name "/SCLK") (class "Default")
      (node (ref "IC5") (pin "11") (pinfunction "SCK_11") (pintype "input"))
      (node (ref "ICA") (pin "9") (pinfunction "SCLK_9") (pintype "bidirectional"))
      (node (ref "ICB") (pin "9") (pinfunction "SCLK_9") (pintype "bidirectional"))
      (node (ref "ICC") (pin "9") (pinfunction "SCLK_9") (pintype "bidirectional"))
      (node (ref "ICD") (pin "9") (pinfunction "SCLK_9") (pintype "bidirectional"))
      (node (ref "ICE") (pin "9") (pinfunction "SCLK_9") (pintype "bidirectional"))
      (node (ref "ICF") (pin "9") (pinfunction "SCLK_9") (pintype "bidirectional"))
      (node (ref "ICG") (pin "9") (pinfunction "SCLK_9") (pintype "bidirectional"))
      (node (ref "ICH") (pin "9") (pinfunction "SCLK_9") (pintype "bidirectional"))
      (node (ref "ICPOW") (pin "2") (pinfunction "CLK_2") (pintype "bidirectional"))
      (node (ref "U$1") (pin "21") (pinfunction "PA5/SPI1_SCK_21") (pintype "bidirectional"))
    )
    (net (code "61") (name "/SWCLK") (class "Default")
      (node (ref "JP11") (pin "2") (pinfunction "2_2") (pintype "passive"))
      (node (ref "U$1") (pin "49") (pinfunction "PA14/JTCK_49") (pintype "bidirectional"))
    )
    (net (code "62") (name "/SWDIO") (class "Default")
      (node (ref "JP11") (pin "3") (pinfunction "3_3") (pintype "passive"))
      (node (ref "SWDIO") (pin "2") (pinfunction "2_2") (pintype "passive"))
    )
    (net (code "63") (name "/URX1") (class "Default")
      (node (ref "JP10") (pin "4") (pinfunction "4_4") (pintype "passive"))
      (node (ref "U$1") (pin "43") (pinfunction "PA10/UART1_RX_43") (pintype "bidirectional"))
      (node (ref "URXL1") (pin "A") (pinfunction "A_A") (pintype "passive"))
    )
    (net (code "64") (name "/URX2") (class "Default")
      (node (ref "JP9") (pin "5") (pinfunction "5_5") (pintype "passive"))
      (node (ref "U$1") (pin "17") (pinfunction "PA3/UART2_RX_17") (pintype "bidirectional"))
      (node (ref "URXL2") (pin "A") (pinfunction "A_A") (pintype "passive"))
    )
    (net (code "65") (name "/UTX1") (class "Default")
      (node (ref "JP10") (pin "5") (pinfunction "5_5") (pintype "passive"))
      (node (ref "U$1") (pin "42") (pinfunction "PA9/UART1_TX_42") (pintype "bidirectional"))
      (node (ref "UTXL1") (pin "A") (pinfunction "A_A") (pintype "passive"))
    )
    (net (code "66") (name "/UTX2") (class "Default")
      (node (ref "JP9") (pin "4") (pinfunction "4_4") (pintype "passive"))
      (node (ref "U$1") (pin "16") (pinfunction "PA2/UART2_TX_16") (pintype "bidirectional"))
      (node (ref "UTXL2") (pin "A") (pinfunction "A_A") (pintype "passive"))
    )
    (net (code "67") (name "/W") (class "Default")
      (node (ref "C13") (pin "1") (pinfunction "1_1") (pintype "passive"))
      (node (ref "IC3") (pin "3") (pinfunction "IN+_3") (pintype "input"))
      (node (ref "ICA") (pin "3") (pinfunction "W_3") (pintype "bidirectional"))
      (node (ref "ICB") (pin "3") (pinfunction "W_3") (pintype "bidirectional"))
      (node (ref "ICC") (pin "3") (pinfunction "W_3") (pintype "bidirectional"))
      (node (ref "ICD") (pin "3") (pinfunction "W_3") (pintype "bidirectional"))
      (node (ref "ICE") (pin "3") (pinfunction "W_3") (pintype "bidirectional"))
      (node (ref "ICF") (pin "3") (pinfunction "W_3") (pintype "bidirectional"))
      (node (ref "ICG") (pin "3") (pinfunction "W_3") (pintype "bidirectional"))
      (node (ref "ICH") (pin "3") (pinfunction "W_3") (pintype "bidirectional"))
      (node (ref "R3") (pin "1") (pinfunction "1_1") (pintype "passive"))
    )
    (net (code "68") (name "GND") (class "Default")
      (node (ref "BOOT0") (pin "3") (pinfunction "3_3") (pintype "passive"))
      (node (ref "BOOT1") (pin "3") (pinfunction "3_3") (pintype "passive"))
      (node (ref "C1") (pin "1") (pinfunction "1_1") (pintype "passive"))
      (node (ref "C10") (pin "1") (pinfunction "1_1") (pintype "passive"))
      (node (ref "C11") (pin "1") (pinfunction "1_1") (pintype "passive"))
      (node (ref "C12") (pin "1") (pinfunction "1_1") (pintype "passive"))
      (node (ref "C13") (pin "2") (pinfunction "2_2") (pintype "passive"))
      (node (ref "C14") (pin "1") (pinfunction "1_1") (pintype "passive"))
      (node (ref "C15") (pin "1") (pinfunction "1_1") (pintype "passive"))
      (node (ref "C16") (pin "1") (pinfunction "1_1") (pintype "passive"))
      (node (ref "C17") (pin "1") (pinfunction "1_1") (pintype "passive"))
      (node (ref "C18") (pin "1") (pinfunction "1_1") (pintype "passive"))
      (node (ref "C19") (pin "1") (pinfunction "1_1") (pintype "passive"))
      (node (ref "C2") (pin "1") (pinfunction "1_1") (pintype "passive"))
      (node (ref "C20") (pin "1") (pinfunction "1_1") (pintype "passive"))
      (node (ref "C21") (pin "1") (pinfunction "1_1") (pintype "passive"))
      (node (ref "C22") (pin "1") (pinfunction "1_1") (pintype "passive"))
      (node (ref "C23") (pin "1") (pinfunction "1_1") (pintype "passive"))
      (node (ref "C24") (pin "1") (pinfunction "1_1") (pintype "passive"))
      (node (ref "C25") (pin "1") (pinfunction "1_1") (pintype "passive"))
      (node (ref "C26") (pin "2") (pinfunction "2_2") (pintype "passive"))
      (node (ref "C27") (pin "2") (pinfunction "2_2") (pintype "passive"))
      (node (ref "C28") (pin "1") (pinfunction "1_1") (pintype "passive"))
      (node (ref "C29") (pin "1") (pinfunction "1_1") (pintype "passive"))
      (node (ref "C3") (pin "1") (pinfunction "1_1") (pintype "passive"))
      (node (ref "C4") (pin "1") (pinfunction "1_1") (pintype "passive"))
      (node (ref "C5") (pin "1") (pinfunction "1_1") (pintype "passive"))
      (node (ref "C6") (pin "1") (pinfunction "1_1") (pintype "passive"))
      (node (ref "C7") (pin "1") (pinfunction "1_1") (pintype "passive"))
      (node (ref "C8") (pin "1") (pinfunction "1_1") (pintype "passive"))
      (node (ref "C9") (pin "1") (pinfunction "1_1") (pintype "passive"))
      (node (ref "IC4") (pin "4") (pinfunction "V-_4") (pintype "power_in"))
      (node (ref "IC4") (pin "5") (pinfunction "IN+_5") (pintype "input"))
      (node (ref "IC4") (pin "6") (pinfunction "IN-_6") (pintype "input"))
      (node (ref "IC5") (pin "13") (pinfunction "G_13") (pintype "input"))
      (node (ref "IC5") (pin "8") (pinfunction "GND_8") (pintype "power_in"))
      (node (ref "ICA") (pin "6") (pinfunction "GND_6") (pintype "bidirectional"))
      (node (ref "ICB") (pin "6") (pinfunction "GND_6") (pintype "bidirectional"))
      (node (ref "ICC") (pin "6") (pinfunction "GND_6") (pintype "bidirectional"))
      (node (ref "ICD") (pin "6") (pinfunction "GND_6") (pintype "bidirectional"))
      (node (ref "ICE") (pin "6") (pinfunction "GND_6") (pintype "bidirectional"))
      (node (ref "ICF") (pin "6") (pinfunction "GND_6") (pintype "bidirectional"))
      (node (ref "ICG") (pin "6") (pinfunction "GND_6") (pintype "bidirectional"))
      (node (ref "ICH") (pin "6") (pinfunction "GND_6") (pintype "bidirectional"))
      (node (ref "ICPOW") (pin "5") (pinfunction "GND_5") (pintype "bidirectional"))
      (node (ref "ICSW") (pin "4") (pinfunction "GND_4") (pintype "bidirectional"))
      (node (ref "JP10") (pin "2") (pinfunction "2_2") (pintype "passive"))
      (node (ref "JP10") (pin "6") (pinfunction "6_6") (pintype "passive"))
      (node (ref "JP11") (pin "5") (pinfunction "5_5") (pintype "passive"))
      (node (ref "JP11") (pin "6") (pinfunction "6_6") (pintype "passive"))
      (node (ref "JP9") (pin "2") (pinfunction "2_2") (pintype "passive"))
      (node (ref "JP9") (pin "6") (pinfunction "6_6") (pintype "passive"))
      (node (ref "P30") (pin "1") (pinfunction "1_1") (pintype "passive"))
      (node (ref "P31") (pin "1") (pinfunction "1_1") (pintype "passive"))
      (node (ref "P46") (pin "1") (pinfunction "1_1") (pintype "passive"))
      (node (ref "P47") (pin "1") (pinfunction "1_1") (pintype "passive"))
      (node (ref "R1") (pin "1") (pinfunction "1_1") (pintype "passive"))
      (node (ref "R11") (pin "2") (pinfunction "2_2") (pintype "passive"))
      (node (ref "R15") (pin "2") (pinfunction "2_2") (pintype "passive"))
      (node (ref "R19") (pin "2") (pinfunction "2_2") (pintype "passive"))
      (node (ref "R23") (pin "2") (pinfunction "2_2") (pintype "passive"))
      (node (ref "R27") (pin "2") (pinfunction "2_2") (pintype "passive"))
      (node (ref "R31") (pin "2") (pinfunction "2_2") (pintype "passive"))
      (node (ref "R35") (pin "2") (pinfunction "2_2") (pintype "passive"))
      (node (ref "R39") (pin "2") (pinfunction "2_2") (pintype "passive"))
      (node (ref "R4") (pin "1") (pinfunction "1_1") (pintype "passive"))
      (node (ref "R41") (pin "1") (pinfunction "1_1") (pintype "passive"))
      (node (ref "R42") (pin "1") (pinfunction "1_1") (pintype "passive"))
      (node (ref "R43") (pin "1") (pinfunction "1_1") (pintype "passive"))
      (node (ref "R44") (pin "1") (pinfunction "1_1") (pintype "passive"))
      (node (ref "R47") (pin "1") (pinfunction "1_1") (pintype "passive"))
      (node (ref "R48") (pin "1") (pinfunction "1_1") (pintype "passive"))
      (node (ref "R49") (pin "1") (pinfunction "1_1") (pintype "passive"))
      (node (ref "R5") (pin "1") (pinfunction "1_1") (pintype "passive"))
      (node (ref "R50") (pin "1") (pinfunction "1_1") (pintype "passive"))
      (node (ref "R6") (pin "1") (pinfunction "1_1") (pintype "passive"))
      (node (ref "R7") (pin "1") (pinfunction "1_1") (pintype "passive"))
      (node (ref "R8") (pin "1") (pinfunction "1_1") (pintype "passive"))
      (node (ref "SW1") (pin "1") (pinfunction "1_1") (pintype "passive"))
      (node (ref "U$1") (pin "12") (pinfunction "VSSA_12") (pintype "bidirectional"))
      (node (ref "U$1") (pin "18") (pinfunction "VSS1_18") (pintype "bidirectional"))
      (node (ref "U$1") (pin "63") (pinfunction "VSS2_63") (pintype "bidirectional"))
      (node (ref "U1") (pin "1") (pinfunction "GND_1") (pintype "power_in"))
      (node (ref "U2") (pin "2") (pinfunction "GND_2") (pintype "power_in"))
      (node (ref "X1") (pin "2") (pinfunction "2_2") (pintype "passive"))
      (node (ref "X1") (pin "4") (pinfunction "4_4") (pintype "passive"))
    )
    (net (code "69") (name "Net-(BIPOUT+-PadC)") (class "Default")
      (node (ref "BIPOUT+") (pin "C") (pinfunction "C_C") (pintype "passive"))
      (node (ref "R6") (pin "2") (pinfunction "2_2") (pintype "passive"))
    )
    (net (code "70") (name "Net-(BIPOUT--PadA)") (class "Default")
      (node (ref "BIPOUT-") (pin "A") (pinfunction "A_A") (pintype "passive"))
      (node (ref "R7") (pin "2") (pinfunction "2_2") (pintype "passive"))
    )
    (net (code "71") (name "Net-(BOOT0-Pad2)") (class "Default")
      (node (ref "BOOT0") (pin "2") (pinfunction "2_2") (pintype "passive"))
      (node (ref "R51") (pin "1") (pinfunction "1_1") (pintype "passive"))
    )
    (net (code "72") (name "Net-(BOOT1-Pad2)") (class "Default")
      (node (ref "BOOT1") (pin "2") (pinfunction "2_2") (pintype "passive"))
      (node (ref "R52") (pin "1") (pinfunction "1_1") (pintype "passive"))
    )
    (net (code "73") (name "Net-(C18-Pad2)") (class "Default")
      (node (ref "C18") (pin "2") (pinfunction "2_2") (pintype "passive"))
      (node (ref "P31") (pin "3") (pinfunction "3_3") (pintype "passive"))
    )
    (net (code "74") (name "Net-(C19-Pad2)") (class "Default")
      (node (ref "C19") (pin "2") (pinfunction "2_2") (pintype "passive"))
      (node (ref "P46") (pin "3") (pinfunction "3_3") (pintype "passive"))
    )
    (net (code "75") (name "Net-(C21-Pad2)") (class "Default")
      (node (ref "C21") (pin "2") (pinfunction "2_2") (pintype "passive"))
      (node (ref "P47") (pin "3") (pinfunction "3_3") (pintype "passive"))
    )
    (net (code "76") (name "Net-(C24-Pad2)") (class "Default")
      (node (ref "C24") (pin "2") (pinfunction "2_2") (pintype "passive"))
      (node (ref "P30") (pin "3") (pinfunction "3_3") (pintype "passive"))
    )
    (net (code "77") (name "Net-(IC3A-IN-)") (class "Default")
      (node (ref "IC3") (pin "2") (pinfunction "IN-_2") (pintype "input"))
      (node (ref "R1") (pin "2") (pinfunction "2_2") (pintype "passive"))
      (node (ref "R2") (pin "1") (pinfunction "1_1") (pintype "passive"))
    )
    (net (code "78") (name "Net-(IC3A-OUT)") (class "Default")
      (node (ref "IC3") (pin "1") (pinfunction "OUT_1") (pintype "output"))
      (node (ref "IC3") (pin "5") (pinfunction "IN+_5") (pintype "input"))
      (node (ref "R2") (pin "2") (pinfunction "2_2") (pintype "passive"))
      (node (ref "R3") (pin "2") (pinfunction "2_2") (pintype "passive"))
    )
    (net (code "79") (name "Net-(IC6A-IN+)") (class "Default")
      (node (ref "IC6") (pin "3") (pinfunction "IN+_3") (pintype "input"))
      (node (ref "R10") (pin "1") (pinfunction "1_1") (pintype "passive"))
      (node (ref "R11") (pin "1") (pinfunction "1_1") (pintype "passive"))
    )
    (net (code "80") (name "Net-(IC6A-IN-)") (class "Default")
      (node (ref "IC6") (pin "2") (pinfunction "IN-_2") (pintype "input"))
      (node (ref "R12") (pin "2") (pinfunction "2_2") (pintype "passive"))
      (node (ref "R9") (pin "1") (pinfunction "1_1") (pintype "passive"))
    )
    (net (code "81") (name "Net-(IC6B-IN+)") (class "Default")
      (node (ref "IC6") (pin "5") (pinfunction "IN+_5") (pintype "input"))
      (node (ref "R14") (pin "1") (pinfunction "1_1") (pintype "passive"))
      (node (ref "R15") (pin "1") (pinfunction "1_1") (pintype "passive"))
    )
    (net (code "82") (name "Net-(IC6B-IN-)") (class "Default")
      (node (ref "IC6") (pin "6") (pinfunction "IN-_6") (pintype "input"))
      (node (ref "R13") (pin "1") (pinfunction "1_1") (pintype "passive"))
      (node (ref "R16") (pin "2") (pinfunction "2_2") (pintype "passive"))
    )
    (net (code "83") (name "Net-(IC6C-IN+)") (class "Default")
      (node (ref "IC6") (pin "10") (pinfunction "IN+_10") (pintype "input"))
      (node (ref "R18") (pin "1") (pinfunction "1_1") (pintype "passive"))
      (node (ref "R19") (pin "1") (pinfunction "1_1") (pintype "passive"))
    )
    (net (code "84") (name "Net-(IC6C-IN-)") (class "Default")
      (node (ref "IC6") (pin "9") (pinfunction "IN-_9") (pintype "input"))
      (node (ref "R17") (pin "1") (pinfunction "1_1") (pintype "passive"))
      (node (ref "R20") (pin "2") (pinfunction "2_2") (pintype "passive"))
    )
    (net (code "85") (name "Net-(IC6D-IN+)") (class "Default")
      (node (ref "IC6") (pin "12") (pinfunction "IN+_12") (pintype "input"))
      (node (ref "R22") (pin "1") (pinfunction "1_1") (pintype "passive"))
      (node (ref "R23") (pin "1") (pinfunction "1_1") (pintype "passive"))
    )
    (net (code "86") (name "Net-(IC6D-IN-)") (class "Default")
      (node (ref "IC6") (pin "13") (pinfunction "IN-_13") (pintype "input"))
      (node (ref "R21") (pin "1") (pinfunction "1_1") (pintype "passive"))
      (node (ref "R24") (pin "2") (pinfunction "2_2") (pintype "passive"))
    )
    (net (code "87") (name "Net-(IC7A-IN+)") (class "Default")
      (node (ref "IC7") (pin "3") (pinfunction "IN+_3") (pintype "input"))
      (node (ref "R26") (pin "1") (pinfunction "1_1") (pintype "passive"))
      (node (ref "R27") (pin "1") (pinfunction "1_1") (pintype "passive"))
    )
    (net (code "88") (name "Net-(IC7A-IN-)") (class "Default")
      (node (ref "IC7") (pin "2") (pinfunction "IN-_2") (pintype "input"))
      (node (ref "R25") (pin "1") (pinfunction "1_1") (pintype "passive"))
      (node (ref "R28") (pin "2") (pinfunction "2_2") (pintype "passive"))
    )
    (net (code "89") (name "Net-(IC7B-IN+)") (class "Default")
      (node (ref "IC7") (pin "5") (pinfunction "IN+_5") (pintype "input"))
      (node (ref "R30") (pin "1") (pinfunction "1_1") (pintype "passive"))
      (node (ref "R31") (pin "1") (pinfunction "1_1") (pintype "passive"))
    )
    (net (code "90") (name "Net-(IC7B-IN-)") (class "Default")
      (node (ref "IC7") (pin "6") (pinfunction "IN-_6") (pintype "input"))
      (node (ref "R29") (pin "1") (pinfunction "1_1") (pintype "passive"))
      (node (ref "R32") (pin "2") (pinfunction "2_2") (pintype "passive"))
    )
    (net (code "91") (name "Net-(IC7C-IN+)") (class "Default")
      (node (ref "IC7") (pin "10") (pinfunction "IN+_10") (pintype "input"))
      (node (ref "R34") (pin "1") (pinfunction "1_1") (pintype "passive"))
      (node (ref "R35") (pin "1") (pinfunction "1_1") (pintype "passive"))
    )
    (net (code "92") (name "Net-(IC7C-IN-)") (class "Default")
      (node (ref "IC7") (pin "9") (pinfunction "IN-_9") (pintype "input"))
      (node (ref "R33") (pin "1") (pinfunction "1_1") (pintype "passive"))
      (node (ref "R36") (pin "2") (pinfunction "2_2") (pintype "passive"))
    )
    (net (code "93") (name "Net-(IC7D-IN+)") (class "Default")
      (node (ref "IC7") (pin "12") (pinfunction "IN+_12") (pintype "input"))
      (node (ref "R38") (pin "1") (pinfunction "1_1") (pintype "passive"))
      (node (ref "R39") (pin "1") (pinfunction "1_1") (pintype "passive"))
    )
    (net (code "94") (name "Net-(IC7D-IN-)") (class "Default")
      (node (ref "IC7") (pin "13") (pinfunction "IN-_13") (pintype "input"))
      (node (ref "R37") (pin "1") (pinfunction "1_1") (pintype "passive"))
      (node (ref "R40") (pin "2") (pinfunction "2_2") (pintype "passive"))
    )
    (net (code "95") (name "Net-(ICA-CAP)") (class "Default")
      (node (ref "C14") (pin "2") (pinfunction "2_2") (pintype "passive"))
      (node (ref "ICA") (pin "5") (pinfunction "CAP_5") (pintype "bidirectional"))
    )
    (net (code "96") (name "Net-(ICB-CAP)") (class "Default")
      (node (ref "C2") (pin "2") (pinfunction "2_2") (pintype "passive"))
      (node (ref "ICB") (pin "5") (pinfunction "CAP_5") (pintype "bidirectional"))
    )
    (net (code "97") (name "Net-(ICC-CAP)") (class "Default")
      (node (ref "C3") (pin "2") (pinfunction "2_2") (pintype "passive"))
      (node (ref "ICC") (pin "5") (pinfunction "CAP_5") (pintype "bidirectional"))
    )
    (net (code "98") (name "Net-(ICD-CAP)") (class "Default")
      (node (ref "C4") (pin "2") (pinfunction "2_2") (pintype "passive"))
      (node (ref "ICD") (pin "5") (pinfunction "CAP_5") (pintype "bidirectional"))
    )
    (net (code "99") (name "Net-(ICE-CAP)") (class "Default")
      (node (ref "C5") (pin "2") (pinfunction "2_2") (pintype "passive"))
      (node (ref "ICE") (pin "5") (pinfunction "CAP_5") (pintype "bidirectional"))
    )
    (net (code "100") (name "Net-(ICF-CAP)") (class "Default")
      (node (ref "C6") (pin "2") (pinfunction "2_2") (pintype "passive"))
      (node (ref "ICF") (pin "5") (pinfunction "CAP_5") (pintype "bidirectional"))
    )
    (net (code "101") (name "Net-(ICG-CAP)") (class "Default")
      (node (ref "C7") (pin "2") (pinfunction "2_2") (pintype "passive"))
      (node (ref "ICG") (pin "5") (pinfunction "CAP_5") (pintype "bidirectional"))
    )
    (net (code "102") (name "Net-(ICH-CAP)") (class "Default")
      (node (ref "C1") (pin "2") (pinfunction "2_2") (pintype "passive"))
      (node (ref "ICH") (pin "5") (pinfunction "CAP_5") (pintype "bidirectional"))
    )
    (net (code "103") (name "Net-(LED+2.5-PadC)") (class "Default")
      (node (ref "LED+2.5") (pin "C") (pinfunction "C_C") (pintype "passive"))
      (node (ref "R5") (pin "2") (pinfunction "2_2") (pintype "passive"))
    )
    (net (code "104") (name "Net-(LED-2.5-PadA)") (class "Default")
      (node (ref "LED-2.5") (pin "A") (pinfunction "A_A") (pintype "passive"))
      (node (ref "R4") (pin "2") (pinfunction "2_2") (pintype "passive"))
    )
    (net (code "105") (name "Net-(LEDOUT-PadC)") (class "Default")
      (node (ref "LEDOUT") (pin "C") (pinfunction "C_C") (pintype "passive"))
      (node (ref "R8") (pin "2") (pinfunction "2_2") (pintype "passive"))
    )
    (net (code "106") (name "Net-(PC0-PadC)") (class "Default")
      (node (ref "PC0") (pin "C") (pinfunction "C_C") (pintype "passive"))
      (node (ref "R47") (pin "2") (pinfunction "2_2") (pintype "passive"))
    )
    (net (code "107") (name "Net-(PC1-PadC)") (class "Default")
      (node (ref "PC1") (pin "C") (pinfunction "C_C") (pintype "passive"))
      (node (ref "R48") (pin "2") (pinfunction "2_2") (pintype "passive"))
    )
    (net (code "108") (name "Net-(PC2-PadC)") (class "Default")
      (node (ref "PC2") (pin "C") (pinfunction "C_C") (pintype "passive"))
      (node (ref "R49") (pin "2") (pinfunction "2_2") (pintype "passive"))
    )
    (net (code "109") (name "Net-(PC3-PadC)") (class "Default")
      (node (ref "PC3") (pin "C") (pinfunction "C_C") (pintype "passive"))
      (node (ref "R50") (pin "2") (pinfunction "2_2") (pintype "passive"))
    )
    (net (code "110") (name "Net-(R41-Pad2)") (class "Default")
      (node (ref "R41") (pin "2") (pinfunction "2_2") (pintype "passive"))
      (node (ref "URXL1") (pin "C") (pinfunction "C_C") (pintype "passive"))
    )
    (net (code "111") (name "Net-(R42-Pad2)") (class "Default")
      (node (ref "R42") (pin "2") (pinfunction "2_2") (pintype "passive"))
      (node (ref "UTXL1") (pin "C") (pinfunction "C_C") (pintype "passive"))
    )
    (net (code "112") (name "Net-(R43-Pad2)") (class "Default")
      (node (ref "R43") (pin "2") (pinfunction "2_2") (pintype "passive"))
      (node (ref "UTXL2") (pin "C") (pinfunction "C_C") (pintype "passive"))
    )
    (net (code "113") (name "Net-(R44-Pad2)") (class "Default")
      (node (ref "R44") (pin "2") (pinfunction "2_2") (pintype "passive"))
      (node (ref "URXL2") (pin "C") (pinfunction "C_C") (pintype "passive"))
    )
    (net (code "114") (name "Net-(U$1-PC0)") (class "Default")
      (node (ref "PC0") (pin "A") (pinfunction "A_A") (pintype "passive"))
      (node (ref "U$1") (pin "8") (pinfunction "PC0_8") (pintype "bidirectional"))
    )
    (net (code "115") (name "Net-(U$1-PC1)") (class "Default")
      (node (ref "PC1") (pin "A") (pinfunction "A_A") (pintype "passive"))
      (node (ref "U$1") (pin "9") (pinfunction "PC1_9") (pintype "bidirectional"))
    )
    (net (code "116") (name "Net-(U$1-PC2)") (class "Default")
      (node (ref "PC2") (pin "A") (pinfunction "A_A") (pintype "passive"))
      (node (ref "U$1") (pin "10") (pinfunction "PC2_10") (pintype "bidirectional"))
    )
    (net (code "117") (name "Net-(U$1-PC3)") (class "Default")
      (node (ref "PC3") (pin "A") (pinfunction "A_A") (pintype "passive"))
      (node (ref "U$1") (pin "11") (pinfunction "PC3_11") (pintype "bidirectional"))
    )
    (net (code "118") (name "Net-(U1-FB)") (class "Default")
      (node (ref "C10") (pin "2") (pinfunction "2_2") (pintype "passive"))
      (node (ref "U1") (pin "4") (pinfunction "FB_4") (pintype "input"))
    )
    (net (code "119") (name "unconnected-(IC4B-OUT-Pad7)") (class "Default")
      (node (ref "IC4") (pin "7") (pinfunction "OUT_7") (pintype "output"))
    )
    (net (code "120") (name "unconnected-(IC5A-QH*-Pad9)") (class "Default")
      (node (ref "IC5") (pin "9") (pinfunction "QH*_9") (pintype "tri_state"))
    )
    (net (code "121") (name "unconnected-(ICPOW-RDY-Pad15)") (class "Default")
      (node (ref "ICPOW") (pin "15") (pinfunction "RDY_15") (pintype "bidirectional"))
    )
    (net (code "122") (name "unconnected-(ICSW-NC-Pad6)") (class "Default")
      (node (ref "ICSW") (pin "6") (pinfunction "NC_6") (pintype "bidirectional"))
    )
    (net (code "123") (name "unconnected-(U$1-PB3{slash}JTDO-Pad55)") (class "Default")
      (node (ref "U$1") (pin "55") (pinfunction "PB3/JTDO_55") (pintype "bidirectional"))
    )
    (net (code "124") (name "unconnected-(U$1-PB4{slash}JTRST-Pad56)") (class "Default")
      (node (ref "U$1") (pin "56") (pinfunction "PB4/JTRST_56") (pintype "bidirectional"))
    )
    (net (code "125") (name "unconnected-(U$1-PB5-Pad57)") (class "Default")
      (node (ref "U$1") (pin "57") (pinfunction "PB5_57") (pintype "bidirectional"))
    )
    (net (code "126") (name "unconnected-(U$1-PB6-Pad58)") (class "Default")
      (node (ref "U$1") (pin "58") (pinfunction "PB6_58") (pintype "bidirectional"))
    )
    (net (code "127") (name "unconnected-(U$1-PB7-Pad59)") (class "Default")
      (node (ref "U$1") (pin "59") (pinfunction "PB7_59") (pintype "bidirectional"))
    )
    (net (code "128") (name "unconnected-(U$1-PB8-Pad61)") (class "Default")
      (node (ref "U$1") (pin "61") (pinfunction "PB8_61") (pintype "bidirectional"))
    )
    (net (code "129") (name "unconnected-(U$1-PB9-Pad62)") (class "Default")
      (node (ref "U$1") (pin "62") (pinfunction "PB9_62") (pintype "bidirectional"))
    )
    (net (code "130") (name "unconnected-(U$1-PC10{slash}SDIO_D2-Pad51)") (class "Default")
      (node (ref "U$1") (pin "51") (pinfunction "PC10/SDIO_D2_51") (pintype "bidirectional"))
    )
    (net (code "131") (name "unconnected-(U$1-PC11{slash}SDIO_D3-Pad52)") (class "Default")
      (node (ref "U$1") (pin "52") (pinfunction "PC11/SDIO_D3_52") (pintype "bidirectional"))
    )
    (net (code "132") (name "unconnected-(U$1-PC12{slash}SDIO_CLK-Pad53)") (class "Default")
      (node (ref "U$1") (pin "53") (pinfunction "PC12/SDIO_CLK_53") (pintype "bidirectional"))
    )
    (net (code "133") (name "unconnected-(U$1-PC13-Pad2)") (class "Default")
      (node (ref "U$1") (pin "2") (pinfunction "PC13_2") (pintype "bidirectional"))
    )
    (net (code "134") (name "unconnected-(U$1-PD2{slash}SDIO_CMD-Pad54)") (class "Default")
      (node (ref "U$1") (pin "54") (pinfunction "PD2/SDIO_CMD_54") (pintype "bidirectional"))
    )
    (net (code "135") (name "unconnected-(U2-FB-Pad4)") (class "Default")
      (node (ref "U2") (pin "4") (pinfunction "FB_4") (pintype "input"))
    )
  )
)
